# USB_Board.net
KiCad netlist of a schematic drawn in EAGLE
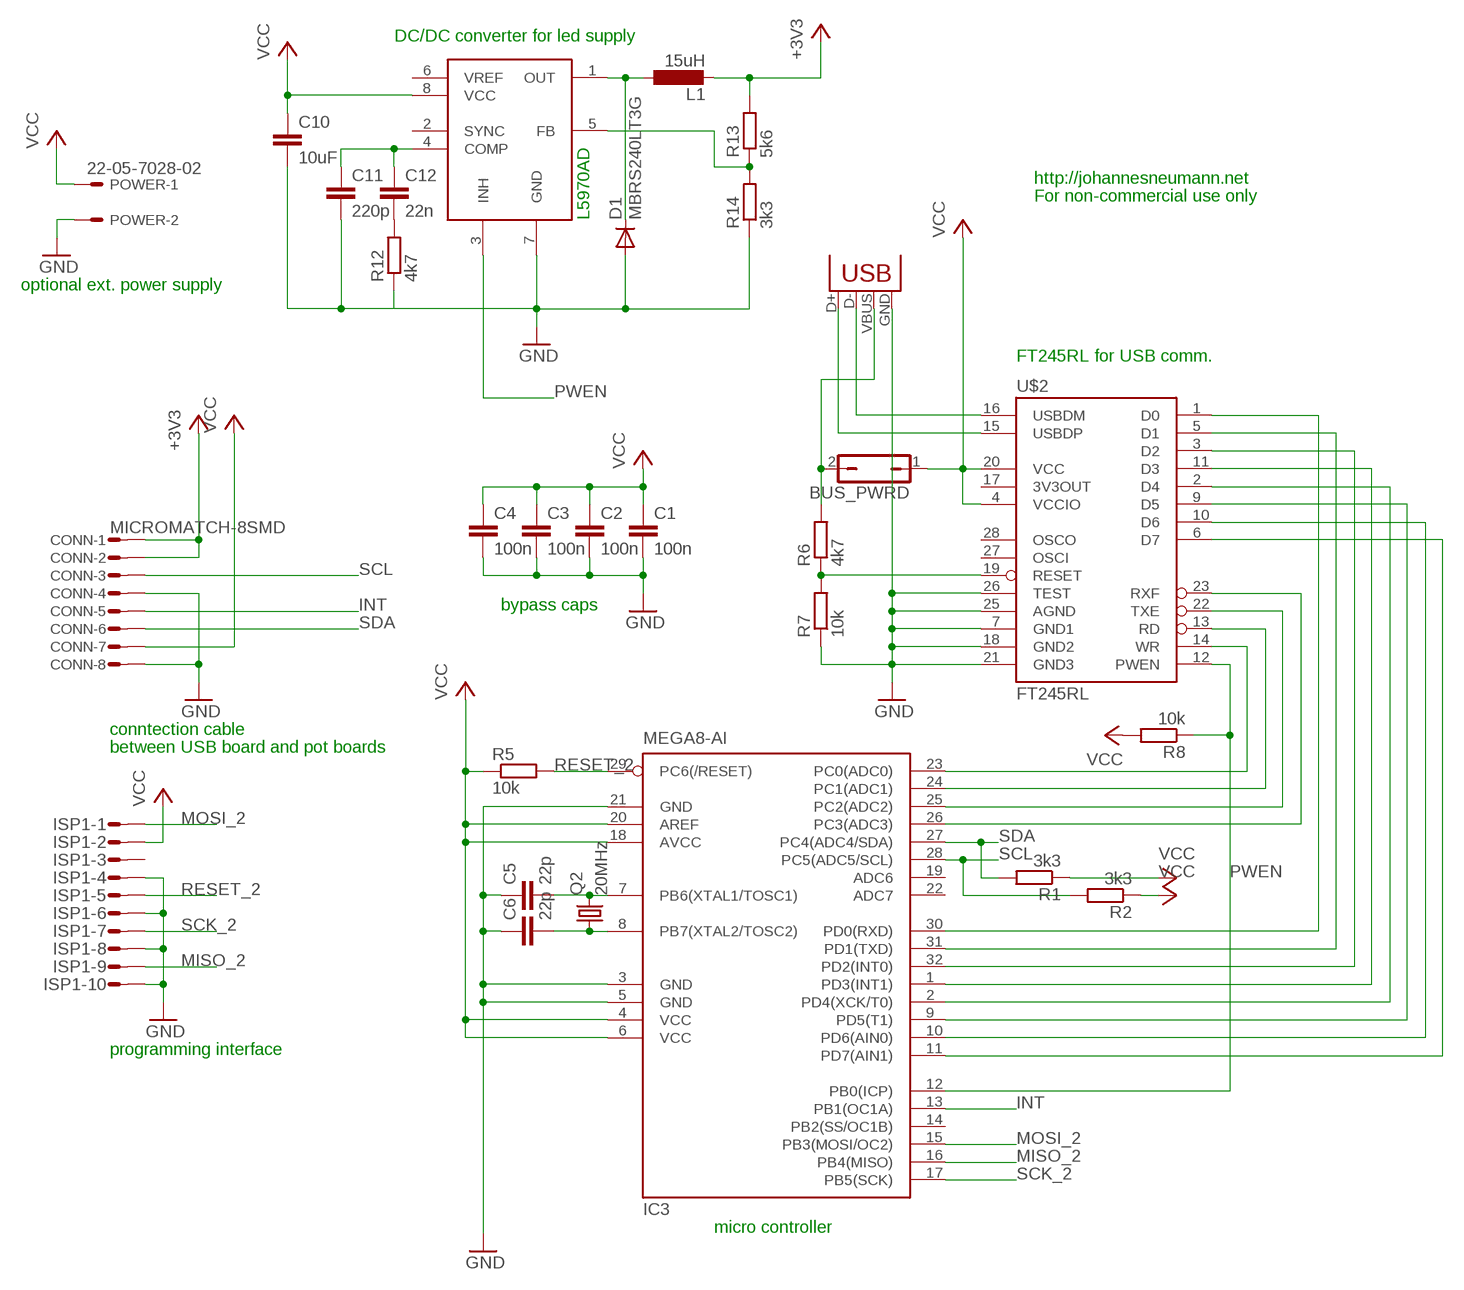
[diagram p0: schematic, sheet 1]

(export (version "E")
  (design (tool "Eeschema 10.0.6"))
  (components
    (comp (ref "BUS_PWRD")
      (value "JP1Q")
      (footprint "eagle-import:JP1")
      (libsource (lib "eagle-import") (part "JP1Q"))
    )
    (comp (ref "C1")
      (value "100n")
      (footprint "eagle-import:C0603")
      (libsource (lib "eagle-import") (part "C-EUC0603"))
    )
    (comp (ref "C2")
      (value "100n")
      (footprint "eagle-import:C0603")
      (libsource (lib "eagle-import") (part "C-EUC0603"))
    )
    (comp (ref "C3")
      (value "100n")
      (footprint "eagle-import:C0603")
      (libsource (lib "eagle-import") (part "C-EUC0603"))
    )
    (comp (ref "C4")
      (value "100n")
      (footprint "eagle-import:C0603")
      (libsource (lib "eagle-import") (part "C-EUC0603"))
    )
    (comp (ref "C5")
      (value "22p")
      (footprint "eagle-import:C0603")
      (libsource (lib "eagle-import") (part "C-EUC0603"))
    )
    (comp (ref "C6")
      (value "22p")
      (footprint "eagle-import:C0603")
      (libsource (lib "eagle-import") (part "C-EUC0603"))
    )
    (comp (ref "C10")
      (value "10uF")
      (footprint "eagle-import:C0805")
      (libsource (lib "eagle-import") (part "C-EUC0805"))
    )
    (comp (ref "C11")
      (value "220p")
      (footprint "eagle-import:C0603")
      (libsource (lib "eagle-import") (part "C-EUC0603"))
    )
    (comp (ref "C12")
      (value "22n")
      (footprint "eagle-import:C0603")
      (libsource (lib "eagle-import") (part "C-EUC0603"))
    )
    (comp (ref "CONN")
      (value "MICROMATCH-8SMD")
      (footprint "eagle-import:MICROMATCH-8-SMD")
      (libsource (lib "eagle-import") (part "MICROMATCH-8SMD"))
    )
    (comp (ref "D1")
      (value "MBRS240LT3G")
      (footprint "eagle-import:DO41-10")
      (libsource (lib "eagle-import") (part "1N4004"))
    )
    (comp (ref "IC3")
      (value "MEGA8-AI")
      (footprint "eagle-import:TQFP32-08")
      (libsource (lib "eagle-import") (part "MEGA8-AI"))
    )
    (comp (ref "ISP1")
      (value "MICROMATCH-10-SMD")
      (footprint "eagle-import:MICROMATCH-10-SMD")
      (libsource (lib "eagle-import") (part "MICROMATCH-10-SMD"))
    )
    (comp (ref "L1")
      (value "15uH")
      (footprint "eagle-import:PIS2816")
      (libsource (lib "eagle-import") (part "L-EUPIS2816"))
    )
    (comp (ref "POWER")
      (value "22-05-7028-02")
      (footprint "eagle-import:7395-02")
      (libsource (lib "eagle-import") (part "22-?-0205-7028"))
    )
    (comp (ref "Q2")
      (value "20MHz")
      (footprint "eagle-import:SM49")
      (libsource (lib "eagle-import") (part "CRYSTALSM49"))
    )
    (comp (ref "R1")
      (value "3k3")
      (footprint "eagle-import:R0603")
      (libsource (lib "eagle-import") (part "R-EU_R0603"))
    )
    (comp (ref "R2")
      (value "3k3")
      (footprint "eagle-import:R0603")
      (libsource (lib "eagle-import") (part "R-EU_R0603"))
    )
    (comp (ref "R5")
      (value "10k")
      (footprint "eagle-import:R0603")
      (libsource (lib "eagle-import") (part "R-EU_R0603"))
    )
    (comp (ref "R6")
      (value "4k7")
      (footprint "eagle-import:R0603")
      (libsource (lib "eagle-import") (part "R-EU_R0603"))
    )
    (comp (ref "R7")
      (value "10k")
      (footprint "eagle-import:R0603")
      (libsource (lib "eagle-import") (part "R-EU_R0603"))
    )
    (comp (ref "R8")
      (value "10k")
      (footprint "eagle-import:R0603")
      (libsource (lib "eagle-import") (part "R-EU_R0603"))
    )
    (comp (ref "R12")
      (value "4k7")
      (footprint "eagle-import:R0603")
      (libsource (lib "eagle-import") (part "R-EU_R0603"))
    )
    (comp (ref "R13")
      (value "5k6")
      (footprint "eagle-import:R0603")
      (libsource (lib "eagle-import") (part "R-EU_R0603"))
    )
    (comp (ref "R14")
      (value "3k3")
      (footprint "eagle-import:R0603")
      (libsource (lib "eagle-import") (part "R-EU_R0603"))
    )
    (comp (ref "U$2")
      (value "FT245RL")
      (footprint "eagle-import:SSOP28DB")
      (libsource (lib "eagle-import") (part "FT245RL"))
    )
    (comp (ref "U$3")
      (value "L5970AD")
      (footprint "eagle-import:SO8")
      (libsource (lib "eagle-import") (part "L5970AD"))
    )
    (comp (ref "X1")
      (value "USBPTH")
      (footprint "eagle-import:USB-B-PTH")
      (libsource (lib "eagle-import") (part "USBPTH"))
    )
  )
  (nets
    (net (code "1") (name "+3V3") (class "Default")
      (node (ref "CONN") (pin "1") (pinfunction "S_1") (pintype "passive"))
      (node (ref "CONN") (pin "2") (pinfunction "S_2") (pintype "passive"))
      (node (ref "L1") (pin "2") (pinfunction "2_2") (pintype "passive"))
      (node (ref "R13") (pin "2") (pinfunction "2_2") (pintype "passive"))
    )
    (net (code "2") (name "/INT") (class "Default")
      (node (ref "CONN") (pin "5") (pinfunction "S_5") (pintype "passive"))
      (node (ref "IC3") (pin "13") (pinfunction "PB1(OC1A)_13") (pintype "bidirectional"))
    )
    (net (code "3") (name "/MISO_2") (class "Default")
      (node (ref "IC3") (pin "16") (pinfunction "PB4(MISO)_16") (pintype "bidirectional"))
      (node (ref "ISP1") (pin "P$9") (pinfunction "S_P$9") (pintype "passive"))
    )
    (net (code "4") (name "/MOSI_2") (class "Default")
      (node (ref "IC3") (pin "15") (pinfunction "PB3(MOSI/OC2)_15") (pintype "bidirectional"))
      (node (ref "ISP1") (pin "P$1") (pinfunction "S_P$1") (pintype "passive"))
    )
    (net (code "5") (name "/PWEN") (class "Default")
      (node (ref "IC3") (pin "12") (pinfunction "PB0(ICP)_12") (pintype "bidirectional"))
      (node (ref "R8") (pin "1") (pinfunction "1_1") (pintype "passive"))
      (node (ref "U$2") (pin "12") (pinfunction "PWEN_12") (pintype "bidirectional"))
      (node (ref "U$3") (pin "3") (pinfunction "INH_3") (pintype "bidirectional"))
    )
    (net (code "6") (name "/RESET_2") (class "Default")
      (node (ref "IC3") (pin "29") (pinfunction "PC6(/RESET)_29") (pintype "bidirectional"))
      (node (ref "ISP1") (pin "P$5") (pinfunction "S_P$5") (pintype "passive"))
      (node (ref "R5") (pin "2") (pinfunction "2_2") (pintype "passive"))
    )
    (net (code "7") (name "/SCK_2") (class "Default")
      (node (ref "IC3") (pin "17") (pinfunction "PB5(SCK)_17") (pintype "bidirectional"))
      (node (ref "ISP1") (pin "P$7") (pinfunction "S_P$7") (pintype "passive"))
    )
    (net (code "8") (name "/SCL") (class "Default")
      (node (ref "CONN") (pin "3") (pinfunction "S_3") (pintype "passive"))
      (node (ref "IC3") (pin "28") (pinfunction "PC5(ADC5/SCL)_28") (pintype "bidirectional"))
      (node (ref "R2") (pin "2") (pinfunction "2_2") (pintype "passive"))
    )
    (net (code "9") (name "/SDA") (class "Default")
      (node (ref "CONN") (pin "6") (pinfunction "S_6") (pintype "passive"))
      (node (ref "IC3") (pin "27") (pinfunction "PC4(ADC4/SDA)_27") (pintype "bidirectional"))
      (node (ref "R1") (pin "2") (pinfunction "2_2") (pintype "passive"))
    )
    (net (code "10") (name "GND") (class "Default")
      (node (ref "C1") (pin "2") (pinfunction "2_2") (pintype "passive"))
      (node (ref "C10") (pin "2") (pinfunction "2_2") (pintype "passive"))
      (node (ref "C11") (pin "2") (pinfunction "2_2") (pintype "passive"))
      (node (ref "C2") (pin "2") (pinfunction "2_2") (pintype "passive"))
      (node (ref "C3") (pin "2") (pinfunction "2_2") (pintype "passive"))
      (node (ref "C4") (pin "2") (pinfunction "2_2") (pintype "passive"))
      (node (ref "C5") (pin "1") (pinfunction "1_1") (pintype "passive"))
      (node (ref "C6") (pin "1") (pinfunction "1_1") (pintype "passive"))
      (node (ref "CONN") (pin "4") (pinfunction "S_4") (pintype "passive"))
      (node (ref "CONN") (pin "8") (pinfunction "S_8") (pintype "passive"))
      (node (ref "D1") (pin "A") (pinfunction "A_A") (pintype "passive"))
      (node (ref "IC3") (pin "21") (pinfunction "GND_21") (pintype "power_in"))
      (node (ref "IC3") (pin "3") (pinfunction "GND_3") (pintype "power_in"))
      (node (ref "IC3") (pin "5") (pinfunction "GND_5") (pintype "power_in"))
      (node (ref "ISP1") (pin "P$10") (pinfunction "S_P$10") (pintype "passive"))
      (node (ref "ISP1") (pin "P$4") (pinfunction "S_P$4") (pintype "passive"))
      (node (ref "ISP1") (pin "P$6") (pinfunction "S_P$6") (pintype "passive"))
      (node (ref "ISP1") (pin "P$8") (pinfunction "S_P$8") (pintype "passive"))
      (node (ref "POWER") (pin "2") (pinfunction "S_2") (pintype "passive"))
      (node (ref "R12") (pin "1") (pinfunction "1_1") (pintype "passive"))
      (node (ref "R14") (pin "1") (pinfunction "1_1") (pintype "passive"))
      (node (ref "R7") (pin "1") (pinfunction "1_1") (pintype "passive"))
      (node (ref "U$2") (pin "18") (pinfunction "GND2_18") (pintype "power_in"))
      (node (ref "U$2") (pin "21") (pinfunction "GND3_21") (pintype "power_in"))
      (node (ref "U$2") (pin "25") (pinfunction "AGND_25") (pintype "power_in"))
      (node (ref "U$2") (pin "26") (pinfunction "TEST_26") (pintype "input"))
      (node (ref "U$2") (pin "7") (pinfunction "GND1_7") (pintype "power_in"))
      (node (ref "U$3") (pin "7") (pinfunction "GND_7") (pintype "bidirectional"))
      (node (ref "X1") (pin "GND") (pinfunction "GND_GND") (pintype "bidirectional"))
    )
    (net (code "11") (name "Net-(BUS_PWRD-Pad2)") (class "Default")
      (node (ref "BUS_PWRD") (pin "2") (pinfunction "2_2") (pintype "passive"))
      (node (ref "R6") (pin "2") (pinfunction "2_2") (pintype "passive"))
      (node (ref "X1") (pin "VBUS") (pinfunction "VBUS_VBUS") (pintype "bidirectional"))
    )
    (net (code "12") (name "Net-(C12-Pad2)") (class "Default")
      (node (ref "C12") (pin "2") (pinfunction "2_2") (pintype "passive"))
      (node (ref "R12") (pin "2") (pinfunction "2_2") (pintype "passive"))
    )
    (net (code "13") (name "Net-(IC3-PB6(XTAL1{slash}TOSC1))") (class "Default")
      (node (ref "C5") (pin "2") (pinfunction "2_2") (pintype "passive"))
      (node (ref "IC3") (pin "7") (pinfunction "PB6(XTAL1/TOSC1)_7") (pintype "bidirectional"))
      (node (ref "Q2") (pin "2") (pinfunction "2_2") (pintype "passive"))
    )
    (net (code "14") (name "Net-(IC3-PB7(XTAL2{slash}TOSC2))") (class "Default")
      (node (ref "C6") (pin "2") (pinfunction "2_2") (pintype "passive"))
      (node (ref "IC3") (pin "8") (pinfunction "PB7(XTAL2/TOSC2)_8") (pintype "bidirectional"))
      (node (ref "Q2") (pin "1") (pinfunction "1_1") (pintype "passive"))
    )
    (net (code "15") (name "Net-(IC3-PC0(ADC0))") (class "Default")
      (node (ref "IC3") (pin "23") (pinfunction "PC0(ADC0)_23") (pintype "bidirectional"))
      (node (ref "U$2") (pin "14") (pinfunction "WR_14") (pintype "bidirectional"))
    )
    (net (code "16") (name "Net-(IC3-PC1(ADC1))") (class "Default")
      (node (ref "IC3") (pin "24") (pinfunction "PC1(ADC1)_24") (pintype "bidirectional"))
      (node (ref "U$2") (pin "13") (pinfunction "RD_13") (pintype "bidirectional"))
    )
    (net (code "17") (name "Net-(IC3-PC2(ADC2))") (class "Default")
      (node (ref "IC3") (pin "25") (pinfunction "PC2(ADC2)_25") (pintype "bidirectional"))
      (node (ref "U$2") (pin "22") (pinfunction "TXE_22") (pintype "bidirectional"))
    )
    (net (code "18") (name "Net-(IC3-PC3(ADC3))") (class "Default")
      (node (ref "IC3") (pin "26") (pinfunction "PC3(ADC3)_26") (pintype "bidirectional"))
      (node (ref "U$2") (pin "23") (pinfunction "RXF_23") (pintype "bidirectional"))
    )
    (net (code "19") (name "Net-(IC3-PD0(RXD))") (class "Default")
      (node (ref "IC3") (pin "30") (pinfunction "PD0(RXD)_30") (pintype "bidirectional"))
      (node (ref "U$2") (pin "1") (pinfunction "D0_1") (pintype "output"))
    )
    (net (code "20") (name "Net-(IC3-PD1(TXD))") (class "Default")
      (node (ref "IC3") (pin "31") (pinfunction "PD1(TXD)_31") (pintype "bidirectional"))
      (node (ref "U$2") (pin "5") (pinfunction "D1_5") (pintype "input"))
    )
    (net (code "21") (name "Net-(IC3-PD2(INT0))") (class "Default")
      (node (ref "IC3") (pin "32") (pinfunction "PD2(INT0)_32") (pintype "bidirectional"))
      (node (ref "U$2") (pin "3") (pinfunction "D2_3") (pintype "output"))
    )
    (net (code "22") (name "Net-(IC3-PD3(INT1))") (class "Default")
      (node (ref "IC3") (pin "1") (pinfunction "PD3(INT1)_1") (pintype "bidirectional"))
      (node (ref "U$2") (pin "11") (pinfunction "D3_11") (pintype "input"))
    )
    (net (code "23") (name "Net-(IC3-PD4(XCK{slash}T0))") (class "Default")
      (node (ref "IC3") (pin "2") (pinfunction "PD4(XCK/T0)_2") (pintype "bidirectional"))
      (node (ref "U$2") (pin "2") (pinfunction "D4_2") (pintype "output"))
    )
    (net (code "24") (name "Net-(IC3-PD5(T1))") (class "Default")
      (node (ref "IC3") (pin "9") (pinfunction "PD5(T1)_9") (pintype "bidirectional"))
      (node (ref "U$2") (pin "9") (pinfunction "D5_9") (pintype "input"))
    )
    (net (code "25") (name "Net-(IC3-PD6(AIN0))") (class "Default")
      (node (ref "IC3") (pin "10") (pinfunction "PD6(AIN0)_10") (pintype "bidirectional"))
      (node (ref "U$2") (pin "10") (pinfunction "D6_10") (pintype "input"))
    )
    (net (code "26") (name "Net-(IC3-PD7(AIN1))") (class "Default")
      (node (ref "IC3") (pin "11") (pinfunction "PD7(AIN1)_11") (pintype "bidirectional"))
      (node (ref "U$2") (pin "6") (pinfunction "D7_6") (pintype "input"))
    )
    (net (code "27") (name "Net-(U$2-RESET)") (class "Default")
      (node (ref "R6") (pin "1") (pinfunction "1_1") (pintype "passive"))
      (node (ref "R7") (pin "2") (pinfunction "2_2") (pintype "passive"))
      (node (ref "U$2") (pin "19") (pinfunction "RESET_19") (pintype "input"))
    )
    (net (code "28") (name "Net-(U$2-USBDM)") (class "Default")
      (node (ref "U$2") (pin "16") (pinfunction "USBDM_16") (pintype "bidirectional"))
      (node (ref "X1") (pin "D-") (pinfunction "D-_D-") (pintype "bidirectional"))
    )
    (net (code "29") (name "Net-(U$2-USBDP)") (class "Default")
      (node (ref "U$2") (pin "15") (pinfunction "USBDP_15") (pintype "bidirectional"))
      (node (ref "X1") (pin "D+") (pinfunction "D+_D+") (pintype "bidirectional"))
    )
    (net (code "30") (name "Net-(U$3-COMP)") (class "Default")
      (node (ref "C11") (pin "1") (pinfunction "1_1") (pintype "passive"))
      (node (ref "C12") (pin "1") (pinfunction "1_1") (pintype "passive"))
      (node (ref "U$3") (pin "4") (pinfunction "COMP_4") (pintype "bidirectional"))
    )
    (net (code "31") (name "Net-(U$3-FB)") (class "Default")
      (node (ref "R13") (pin "1") (pinfunction "1_1") (pintype "passive"))
      (node (ref "R14") (pin "2") (pinfunction "2_2") (pintype "passive"))
      (node (ref "U$3") (pin "5") (pinfunction "FB_5") (pintype "bidirectional"))
    )
    (net (code "32") (name "Net-(U$3-OUT)") (class "Default")
      (node (ref "D1") (pin "C") (pinfunction "C_C") (pintype "passive"))
      (node (ref "L1") (pin "1") (pinfunction "1_1") (pintype "passive"))
      (node (ref "U$3") (pin "1") (pinfunction "OUT_1") (pintype "bidirectional"))
    )
    (net (code "33") (name "VCC") (class "Default")
      (node (ref "BUS_PWRD") (pin "1") (pinfunction "1_1") (pintype "passive"))
      (node (ref "C1") (pin "1") (pinfunction "1_1") (pintype "passive"))
      (node (ref "C10") (pin "1") (pinfunction "1_1") (pintype "passive"))
      (node (ref "C2") (pin "1") (pinfunction "1_1") (pintype "passive"))
      (node (ref "C3") (pin "1") (pinfunction "1_1") (pintype "passive"))
      (node (ref "C4") (pin "1") (pinfunction "1_1") (pintype "passive"))
      (node (ref "CONN") (pin "7") (pinfunction "S_7") (pintype "passive"))
      (node (ref "IC3") (pin "18") (pinfunction "AVCC_18") (pintype "power_in"))
      (node (ref "IC3") (pin "20") (pinfunction "AREF_20") (pintype "passive"))
      (node (ref "IC3") (pin "4") (pinfunction "VCC_4") (pintype "power_in"))
      (node (ref "IC3") (pin "6") (pinfunction "VCC_6") (pintype "power_in"))
      (node (ref "ISP1") (pin "P$2") (pinfunction "S_P$2") (pintype "passive"))
      (node (ref "POWER") (pin "1") (pinfunction "S_1") (pintype "passive"))
      (node (ref "R1") (pin "1") (pinfunction "1_1") (pintype "passive"))
      (node (ref "R2") (pin "1") (pinfunction "1_1") (pintype "passive"))
      (node (ref "R5") (pin "1") (pinfunction "1_1") (pintype "passive"))
      (node (ref "R8") (pin "2") (pinfunction "2_2") (pintype "passive"))
      (node (ref "U$2") (pin "20") (pinfunction "VCC_20") (pintype "power_in"))
      (node (ref "U$2") (pin "4") (pinfunction "VCCIO_4") (pintype "power_in"))
      (node (ref "U$3") (pin "8") (pinfunction "VCC_8") (pintype "bidirectional"))
    )
    (net (code "34") (name "unconnected-(IC3-ADC6-Pad19)") (class "Default")
      (node (ref "IC3") (pin "19") (pinfunction "ADC6_19") (pintype "bidirectional"))
    )
    (net (code "35") (name "unconnected-(IC3-ADC7-Pad22)") (class "Default")
      (node (ref "IC3") (pin "22") (pinfunction "ADC7_22") (pintype "bidirectional"))
    )
    (net (code "36") (name "unconnected-(IC3-PB2(SS{slash}OC1B)-Pad14)") (class "Default")
      (node (ref "IC3") (pin "14") (pinfunction "PB2(SS/OC1B)_14") (pintype "bidirectional"))
    )
    (net (code "37") (name "unconnected-(ISP1D-S-PadP$3)") (class "Default")
      (node (ref "ISP1") (pin "P$3") (pinfunction "S_P$3") (pintype "passive"))
    )
    (net (code "38") (name "unconnected-(U$2-3V3OUT-Pad17)") (class "Default")
      (node (ref "U$2") (pin "17") (pinfunction "3V3OUT_17") (pintype "output"))
    )
    (net (code "39") (name "unconnected-(U$2-OSCI-Pad27)") (class "Default")
      (node (ref "U$2") (pin "27") (pinfunction "OSCI_27") (pintype "input"))
    )
    (net (code "40") (name "unconnected-(U$2-OSCO-Pad28)") (class "Default")
      (node (ref "U$2") (pin "28") (pinfunction "OSCO_28") (pintype "output"))
    )
    (net (code "41") (name "unconnected-(U$3-SYNC-Pad2)") (class "Default")
      (node (ref "U$3") (pin "2") (pinfunction "SYNC_2") (pintype "bidirectional"))
    )
    (net (code "42") (name "unconnected-(U$3-VREF-Pad6)") (class "Default")
      (node (ref "U$3") (pin "6") (pinfunction "VREF_6") (pintype "bidirectional"))
    )
  )
)
